# m101-power-supply.net
KiCad netlist of a schematic drawn in EAGLE
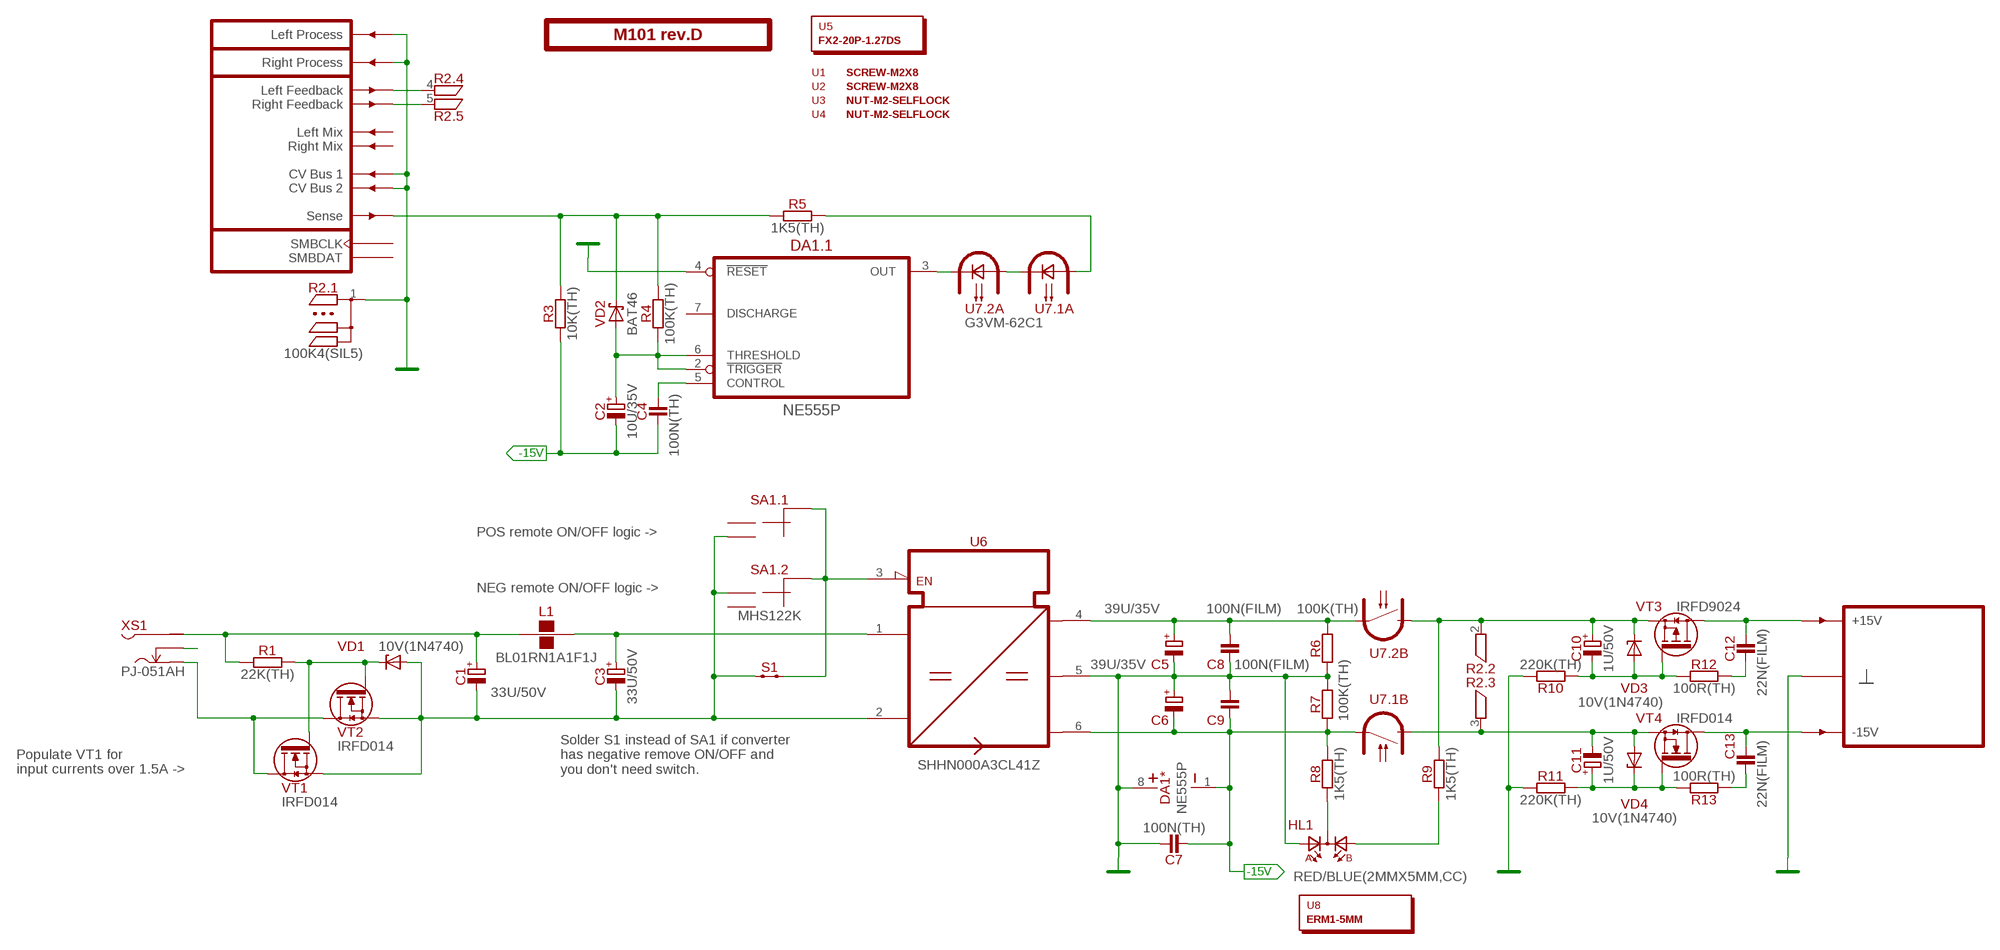
[diagram p0: schematic, sheet 1]

(export (version "E")
  (design (tool "Eeschema 10.0.6"))
  (components
    (comp (ref "C1")
      (value "33U/50V")
      (footprint "eagle-import:E3,5-8")
      (libsource (lib "eagle-import") (part "?33U/50V"))
    )
    (comp (ref "C2")
      (value "10U/35V")
      (footprint "eagle-import:E2-5")
      (libsource (lib "eagle-import") (part "?10U/35V"))
    )
    (comp (ref "C3")
      (value "33U/50V")
      (footprint "eagle-import:E3,5-8")
      (libsource (lib "eagle-import") (part "?33U/50V"))
    )
    (comp (ref "C4")
      (value "100N(TH)")
      (footprint "eagle-import:C050-024X044")
      (libsource (lib "eagle-import") (part "?100N(TH)"))
    )
    (comp (ref "C5")
      (value "39U/35V")
      (footprint "eagle-import:E3,5-8")
      (libsource (lib "eagle-import") (part "?39U/35V"))
    )
    (comp (ref "C6")
      (value "39U/35V")
      (footprint "eagle-import:E3,5-8")
      (libsource (lib "eagle-import") (part "?39U/35V"))
    )
    (comp (ref "C7")
      (value "100N(TH)")
      (footprint "eagle-import:C050-024X044")
      (libsource (lib "eagle-import") (part "?100N(TH)"))
    )
    (comp (ref "C8")
      (value "100N(FILM)")
      (footprint "eagle-import:C050-025X075")
      (libsource (lib "eagle-import") (part "?100N(FILM)"))
    )
    (comp (ref "C9")
      (value "100N(FILM)")
      (footprint "eagle-import:C050-025X075")
      (libsource (lib "eagle-import") (part "?100N(FILM)"))
    )
    (comp (ref "C10")
      (value "1U/50V")
      (footprint "eagle-import:E1,5-4")
      (libsource (lib "eagle-import") (part "?1U/50V"))
    )
    (comp (ref "C11")
      (value "1U/50V")
      (footprint "eagle-import:E1,5-4")
      (libsource (lib "eagle-import") (part "?1U/50V"))
    )
    (comp (ref "C12")
      (value "22N(FILM)")
      (footprint "eagle-import:C050-025X075")
      (libsource (lib "eagle-import") (part "?22N(FILM)"))
    )
    (comp (ref "C13")
      (value "22N(FILM)")
      (footprint "eagle-import:C050-025X075")
      (libsource (lib "eagle-import") (part "?22N(FILM)"))
    )
    (comp (ref "DA1")
      (value "NE555P")
      (footprint "eagle-import:DIP-8")
      (libsource (lib "eagle-import") (part "NE555?P"))
    )
    (comp (ref "HL1")
      (value "RED/BLUE(2MMX5MM,CC)")
      (footprint "eagle-import:LED2X5-3PIN")
      (libsource (lib "eagle-import") (part "?(2MMX5MM,CC)RED/BLUE"))
    )
    (comp (ref "L1")
      (value "BL01RN1A1F1J")
      (footprint "eagle-import:BL01RN1A")
      (libsource (lib "eagle-import") (part "BL01RN1A?1F1J"))
    )
    (comp (ref "PCB1")
      (value "M101 rev.D")
      (footprint "eagle-import:ST2-BOARD-50-PSU")
      (libsource (lib "eagle-import") (part "ST2-BOARD-50-PSU"))
    )
    (comp (ref "R1")
      (value "22K(TH)")
      (footprint "eagle-import:R-0207_10")
      (libsource (lib "eagle-import") (part "?22K(TH)"))
    )
    (comp (ref "R2")
      (value "100K4(SIL5)")
      (footprint "eagle-import:R-SIL5")
      (libsource (lib "eagle-import") (part "?4(SIL5)100K"))
    )
    (comp (ref "R3")
      (value "10K(TH)")
      (footprint "eagle-import:R-0207_10")
      (libsource (lib "eagle-import") (part "?10K(TH)"))
    )
    (comp (ref "R4")
      (value "100K(TH)")
      (footprint "eagle-import:R-0207_10")
      (libsource (lib "eagle-import") (part "?100K(TH)"))
    )
    (comp (ref "R5")
      (value "1K5(TH)")
      (footprint "eagle-import:R-0207_10")
      (libsource (lib "eagle-import") (part "?1K5(TH)"))
    )
    (comp (ref "R6")
      (value "100K(TH)")
      (footprint "eagle-import:R-0207_10")
      (libsource (lib "eagle-import") (part "?100K(TH)"))
    )
    (comp (ref "R7")
      (value "100K(TH)")
      (footprint "eagle-import:R-0207_10")
      (libsource (lib "eagle-import") (part "?100K(TH)"))
    )
    (comp (ref "R8")
      (value "1K5(TH)")
      (footprint "eagle-import:R-0207_10")
      (libsource (lib "eagle-import") (part "?1K5(TH)"))
    )
    (comp (ref "R9")
      (value "1K5(TH)")
      (footprint "eagle-import:R-0207_10")
      (libsource (lib "eagle-import") (part "?1K5(TH)"))
    )
    (comp (ref "R10")
      (value "220K(TH)")
      (footprint "eagle-import:R-0207_10")
      (libsource (lib "eagle-import") (part "?220K(TH)"))
    )
    (comp (ref "R11")
      (value "220K(TH)")
      (footprint "eagle-import:R-0207_10")
      (libsource (lib "eagle-import") (part "?220K(TH)"))
    )
    (comp (ref "R12")
      (value "100R(TH)")
      (footprint "eagle-import:R-0207_10")
      (libsource (lib "eagle-import") (part "?100R(TH)"))
    )
    (comp (ref "R13")
      (value "100R(TH)")
      (footprint "eagle-import:R-0207_10")
      (libsource (lib "eagle-import") (part "?100R(TH)"))
    )
    (comp (ref "S1")
      (value "JUMPER-1POS-SOLDER")
      (footprint "eagle-import:JP1-SOLDER")
      (libsource (lib "eagle-import") (part "JUMPER-1POS-SOLDER"))
    )
    (comp (ref "SA1")
      (value "MHS122K")
      (footprint "eagle-import:APEM-MHS122K")
      (libsource (lib "eagle-import") (part "MHS122K"))
    )
    (comp (ref "U1")
      (value "SCREW-M2X8")
      (footprint "eagle-import:EMPTY")
      (libsource (lib "eagle-import") (part "?SCREW-M2X8"))
    )
    (comp (ref "U2")
      (value "SCREW-M2X8")
      (footprint "eagle-import:EMPTY")
      (libsource (lib "eagle-import") (part "?SCREW-M2X8"))
    )
    (comp (ref "U3")
      (value "NUT-M2-SELFLOCK")
      (footprint "eagle-import:EMPTY")
      (libsource (lib "eagle-import") (part "?NUT-M2-SELFLOCK"))
    )
    (comp (ref "U4")
      (value "NUT-M2-SELFLOCK")
      (footprint "eagle-import:EMPTY")
      (libsource (lib "eagle-import") (part "?NUT-M2-SELFLOCK"))
    )
    (comp (ref "U5")
      (value "FX2-20P-1.27DS")
      (footprint "eagle-import:EMPTY")
      (libsource (lib "eagle-import") (part "?FX2-20P-1.27DS"))
    )
    (comp (ref "U6")
      (value "SHHN000A3CL41Z")
      (footprint "eagle-import:DC_DC-C1")
      (libsource (lib "eagle-import") (part "SHHN000A3CL41Z"))
    )
    (comp (ref "U7")
      (value "G3VM-62C1")
      (footprint "eagle-import:DIL08")
      (libsource (lib "eagle-import") (part "G3VM-?2C61"))
    )
    (comp (ref "U8")
      (value "ERM1-5MM")
      (footprint "eagle-import:EMPTY")
      (libsource (lib "eagle-import") (part "?ERM1-5MM"))
    )
    (comp (ref "VD1")
      (value "10V(1N4740)")
      (footprint "eagle-import:DO41-10")
      (libsource (lib "eagle-import") (part "?10V(1N4740)"))
    )
    (comp (ref "VD2")
      (value "BAT46")
      (footprint "eagle-import:DO35-7")
      (libsource (lib "eagle-import") (part "?BAT46"))
    )
    (comp (ref "VD3")
      (value "10V(1N4740)")
      (footprint "eagle-import:DO41-10")
      (libsource (lib "eagle-import") (part "?10V(1N4740)"))
    )
    (comp (ref "VD4")
      (value "10V(1N4740)")
      (footprint "eagle-import:DO41-10")
      (libsource (lib "eagle-import") (part "?10V(1N4740)"))
    )
    (comp (ref "VT1")
      (value "IRFD014")
      (footprint "eagle-import:HVMDIP-4")
      (libsource (lib "eagle-import") (part "IRFD014"))
    )
    (comp (ref "VT2")
      (value "IRFD014")
      (footprint "eagle-import:HVMDIP-4")
      (libsource (lib "eagle-import") (part "IRFD014"))
    )
    (comp (ref "VT3")
      (value "IRFD9024")
      (footprint "eagle-import:HVMDIP-4")
      (libsource (lib "eagle-import") (part "IRFD9024"))
    )
    (comp (ref "VT4")
      (value "IRFD014")
      (footprint "eagle-import:HVMDIP-4")
      (libsource (lib "eagle-import") (part "IRFD014"))
    )
    (comp (ref "XS1")
      (value "PJ-051AH")
      (footprint "eagle-import:PJ-051AH")
      (libsource (lib "eagle-import") (part "PJ-051?AH"))
    )
  )
  (nets
    (net (code "1") (name "-15V") (class "Default")
      (node (ref "C2") (pin "-") (pinfunction "-_-") (pintype "passive"))
      (node (ref "C4") (pin "1") (pinfunction "1_1") (pintype "passive"))
      (node (ref "C6") (pin "-") (pinfunction "-_-") (pintype "passive"))
      (node (ref "C7") (pin "1") (pinfunction "1_1") (pintype "passive"))
      (node (ref "C9") (pin "1") (pinfunction "1_1") (pintype "passive"))
      (node (ref "DA1") (pin "1") (pinfunction "V-_1") (pintype "power_in"))
      (node (ref "R3") (pin "1") (pinfunction "1_1") (pintype "passive"))
      (node (ref "R7") (pin "1") (pinfunction "1_1") (pintype "passive"))
      (node (ref "R8") (pin "2") (pinfunction "2_2") (pintype "passive"))
      (node (ref "U6") (pin "6") (pinfunction "V-_6") (pintype "power_in"))
      (node (ref "U7") (pin "7") (pinfunction "S2_7") (pintype "passive"))
    )
    (net (code "2") (name "GND") (class "Default")
      (node (ref "C5") (pin "-") (pinfunction "-_-") (pintype "passive"))
      (node (ref "C6") (pin "+") (pinfunction "+_+") (pintype "passive"))
      (node (ref "C7") (pin "2") (pinfunction "2_2") (pintype "passive"))
      (node (ref "C8") (pin "1") (pinfunction "1_1") (pintype "passive"))
      (node (ref "C9") (pin "2") (pinfunction "2_2") (pintype "passive"))
      (node (ref "DA1") (pin "4") (pinfunction "~{RESET}_4") (pintype "input"))
      (node (ref "DA1") (pin "8") (pinfunction "V+_8") (pintype "power_in"))
      (node (ref "HL1") (pin "A1") (pinfunction "A1_A1") (pintype "passive"))
      (node (ref "PCB1") (pin "ACV1'") (pinfunction "CV1'_ACV1'") (pintype "bidirectional"))
      (node (ref "PCB1") (pin "ACV2'") (pinfunction "CV2'_ACV2'") (pintype "bidirectional"))
      (node (ref "PCB1") (pin "B4'") (pinfunction "GND_B4'") (pintype "bidirectional"))
      (node (ref "PCB1") (pin "B5'") (pinfunction "GND_B5'") (pintype "bidirectional"))
      (node (ref "PCB1") (pin "B6'") (pinfunction "GND_B6'") (pintype "bidirectional"))
      (node (ref "PCB1") (pin "B7'") (pinfunction "GND_B7'") (pintype "bidirectional"))
      (node (ref "PCB1") (pin "B8'") (pinfunction "GND_B8'") (pintype "bidirectional"))
      (node (ref "PCB1") (pin "BOUTL'") (pinfunction "OUTL_BOUTL'") (pintype "bidirectional"))
      (node (ref "PCB1") (pin "BOUTR'") (pinfunction "OUTR_BOUTR'") (pintype "bidirectional"))
      (node (ref "R10") (pin "2") (pinfunction "2_2") (pintype "passive"))
      (node (ref "R11") (pin "2") (pinfunction "2_2") (pintype "passive"))
      (node (ref "R2") (pin "1") (pinfunction "R_1") (pintype "passive"))
      (node (ref "R6") (pin "1") (pinfunction "1_1") (pintype "passive"))
      (node (ref "R7") (pin "2") (pinfunction "2_2") (pintype "passive"))
      (node (ref "U6") (pin "5") (pinfunction "GND_5") (pintype "power_in"))
    )
    (net (code "3") (name "Net-(C12-Pad1)") (class "Default")
      (node (ref "C12") (pin "1") (pinfunction "1_1") (pintype "passive"))
      (node (ref "R12") (pin "2") (pinfunction "2_2") (pintype "passive"))
    )
    (net (code "4") (name "Net-(C12-Pad2)") (class "Default")
      (node (ref "C12") (pin "2") (pinfunction "2_2") (pintype "passive"))
      (node (ref "PCB1") (pin "A+15'") (pinfunction "P+15V_A+15'") (pintype "bidirectional"))
      (node (ref "PCB1") (pin "B+15'") (pinfunction "P+15V_B+15'") (pintype "bidirectional"))
      (node (ref "VT3") (pin "1") (pinfunction "D_1") (pintype "bidirectional"))
      (node (ref "VT3") (pin "2") (pinfunction "D_2") (pintype "bidirectional"))
    )
    (net (code "5") (name "Net-(C13-Pad1)") (class "Default")
      (node (ref "C13") (pin "1") (pinfunction "1_1") (pintype "passive"))
      (node (ref "PCB1") (pin "A-15'") (pinfunction "P-15V_A-15'") (pintype "bidirectional"))
      (node (ref "PCB1") (pin "B-15'") (pinfunction "P-15V_B-15'") (pintype "bidirectional"))
      (node (ref "VT4") (pin "1") (pinfunction "D_1") (pintype "bidirectional"))
      (node (ref "VT4") (pin "2") (pinfunction "D_2") (pintype "bidirectional"))
    )
    (net (code "6") (name "Net-(C13-Pad2)") (class "Default")
      (node (ref "C13") (pin "2") (pinfunction "2_2") (pintype "passive"))
      (node (ref "R13") (pin "2") (pinfunction "2_2") (pintype "passive"))
    )
    (net (code "7") (name "Net-(DA1B-CONTROL)") (class "Default")
      (node (ref "C4") (pin "2") (pinfunction "2_2") (pintype "passive"))
      (node (ref "DA1") (pin "5") (pinfunction "CONTROL_5") (pintype "bidirectional"))
    )
    (net (code "8") (name "Net-(DA1B-OUT)") (class "Default")
      (node (ref "DA1") (pin "3") (pinfunction "OUT_3") (pintype "bidirectional"))
      (node (ref "U7") (pin "4") (pinfunction "C_4") (pintype "passive"))
    )
    (net (code "9") (name "Net-(DA1B-THRESHOLD)") (class "Default")
      (node (ref "C2") (pin "+") (pinfunction "+_+") (pintype "passive"))
      (node (ref "DA1") (pin "2") (pinfunction "~{TRIGGER}_2") (pintype "bidirectional"))
      (node (ref "DA1") (pin "6") (pinfunction "THRESHOLD_6") (pintype "bidirectional"))
      (node (ref "R4") (pin "1") (pinfunction "1_1") (pintype "passive"))
      (node (ref "VD2") (pin "A") (pinfunction "A_A") (pintype "passive"))
    )
    (net (code "10") (name "Net-(HL1-PadA2)") (class "Default")
      (node (ref "HL1") (pin "A2") (pinfunction "A2_A2") (pintype "passive"))
      (node (ref "R9") (pin "1") (pinfunction "1_1") (pintype "passive"))
    )
    (net (code "11") (name "Net-(HL1-PadK)") (class "Default")
      (node (ref "HL1") (pin "K") (pinfunction "K_K") (pintype "passive"))
      (node (ref "R8") (pin "1") (pinfunction "1_1") (pintype "passive"))
    )
    (net (code "12") (name "Net-(PCB1D-LFBK')") (class "Default")
      (node (ref "PCB1") (pin "ALFBK'") (pinfunction "LFBK'_ALFBK'") (pintype "bidirectional"))
      (node (ref "R2") (pin "4") (pinfunction "R_4") (pintype "passive"))
    )
    (net (code "13") (name "Net-(PCB1D-RFBK')") (class "Default")
      (node (ref "PCB1") (pin "ARFBK'") (pinfunction "RFBK'_ARFBK'") (pintype "bidirectional"))
      (node (ref "R2") (pin "5") (pinfunction "R_5") (pintype "passive"))
    )
    (net (code "14") (name "Net-(PCB1D-SENSE')") (class "Default")
      (node (ref "PCB1") (pin "BSENSE'") (pinfunction "SENSE'_BSENSE'") (pintype "bidirectional"))
      (node (ref "R3") (pin "2") (pinfunction "2_2") (pintype "passive"))
      (node (ref "R4") (pin "2") (pinfunction "2_2") (pintype "passive"))
      (node (ref "R5") (pin "1") (pinfunction "1_1") (pintype "passive"))
      (node (ref "VD2") (pin "C") (pinfunction "C_C") (pintype "passive"))
    )
    (net (code "15") (name "Net-(R2B-R)") (class "Default")
      (node (ref "C10") (pin "+") (pinfunction "+_+") (pintype "passive"))
      (node (ref "R2") (pin "2") (pinfunction "R_2") (pintype "passive"))
      (node (ref "R9") (pin "2") (pinfunction "2_2") (pintype "passive"))
      (node (ref "U7") (pin "6") (pinfunction "S1_6") (pintype "passive"))
      (node (ref "VD3") (pin "C") (pinfunction "C_C") (pintype "passive"))
      (node (ref "VT3") (pin "4") (pinfunction "S_4") (pintype "bidirectional"))
    )
    (net (code "16") (name "Net-(R2C-R)") (class "Default")
      (node (ref "C11") (pin "-") (pinfunction "-_-") (pintype "passive"))
      (node (ref "R2") (pin "3") (pinfunction "R_3") (pintype "passive"))
      (node (ref "U7") (pin "8") (pinfunction "S1_8") (pintype "passive"))
      (node (ref "VD4") (pin "A") (pinfunction "A_A") (pintype "passive"))
      (node (ref "VT4") (pin "4") (pinfunction "S_4") (pintype "bidirectional"))
    )
    (net (code "17") (name "Net-(SA1A-CM)") (class "Default")
      (node (ref "S1") (pin "2") (pinfunction "2_2") (pintype "passive"))
      (node (ref "SA1") (pin "CMN") (pinfunction "CM_CMN") (pintype "passive"))
      (node (ref "SA1") (pin "CMN'") (pinfunction "CM_CMN'") (pintype "passive"))
      (node (ref "U6") (pin "3") (pinfunction "EN_3") (pintype "bidirectional"))
    )
    (net (code "18") (name "Net-(SA1B-1)") (class "Default")
      (node (ref "C1") (pin "-") (pinfunction "-_-") (pintype "passive"))
      (node (ref "C3") (pin "-") (pinfunction "-_-") (pintype "passive"))
      (node (ref "S1") (pin "1") (pinfunction "1_1") (pintype "passive"))
      (node (ref "SA1") (pin "1'") (pinfunction "1_1'") (pintype "passive"))
      (node (ref "SA1") (pin "2") (pinfunction "2_2") (pintype "passive"))
      (node (ref "U6") (pin "2") (pinfunction "IN-_2") (pintype "power_in"))
      (node (ref "VD1") (pin "A") (pinfunction "A_A") (pintype "passive"))
      (node (ref "VT1") (pin "4") (pinfunction "S_4") (pintype "bidirectional"))
      (node (ref "VT2") (pin "4") (pinfunction "S_4") (pintype "bidirectional"))
    )
    (net (code "19") (name "Net-(U6-IN+)") (class "Default")
      (node (ref "C3") (pin "+") (pinfunction "+_+") (pintype "passive"))
      (node (ref "L1") (pin "2") (pinfunction "2_2") (pintype "passive"))
      (node (ref "U6") (pin "1") (pinfunction "IN+_1") (pintype "power_in"))
    )
    (net (code "20") (name "Net-(U6-V+)") (class "Default")
      (node (ref "C5") (pin "+") (pinfunction "+_+") (pintype "passive"))
      (node (ref "C8") (pin "2") (pinfunction "2_2") (pintype "passive"))
      (node (ref "R6") (pin "2") (pinfunction "2_2") (pintype "passive"))
      (node (ref "U6") (pin "4") (pinfunction "V+_4") (pintype "power_in"))
      (node (ref "U7") (pin "5") (pinfunction "S2_5") (pintype "passive"))
    )
    (net (code "21") (name "Net-(U7A-A)") (class "Default")
      (node (ref "R5") (pin "2") (pinfunction "2_2") (pintype "passive"))
      (node (ref "U7") (pin "1") (pinfunction "A_1") (pintype "passive"))
    )
    (net (code "22") (name "Net-(U7A-C)") (class "Default")
      (node (ref "U7") (pin "2") (pinfunction "C_2") (pintype "passive"))
      (node (ref "U7") (pin "3") (pinfunction "A_3") (pintype "passive"))
    )
    (net (code "23") (name "Net-(VT1-G)") (class "Default")
      (node (ref "R1") (pin "2") (pinfunction "2_2") (pintype "passive"))
      (node (ref "VD1") (pin "C") (pinfunction "C_C") (pintype "passive"))
      (node (ref "VT1") (pin "3") (pinfunction "G_3") (pintype "bidirectional"))
      (node (ref "VT2") (pin "3") (pinfunction "G_3") (pintype "bidirectional"))
    )
    (net (code "24") (name "Net-(VT3-G)") (class "Default")
      (node (ref "C10") (pin "-") (pinfunction "-_-") (pintype "passive"))
      (node (ref "R10") (pin "1") (pinfunction "1_1") (pintype "passive"))
      (node (ref "R12") (pin "1") (pinfunction "1_1") (pintype "passive"))
      (node (ref "VD3") (pin "A") (pinfunction "A_A") (pintype "passive"))
      (node (ref "VT3") (pin "3") (pinfunction "G_3") (pintype "bidirectional"))
    )
    (net (code "25") (name "Net-(VT4-G)") (class "Default")
      (node (ref "C11") (pin "+") (pinfunction "+_+") (pintype "passive"))
      (node (ref "R11") (pin "1") (pinfunction "1_1") (pintype "passive"))
      (node (ref "R13") (pin "1") (pinfunction "1_1") (pintype "passive"))
      (node (ref "VD4") (pin "C") (pinfunction "C_C") (pintype "passive"))
      (node (ref "VT4") (pin "3") (pinfunction "G_3") (pintype "bidirectional"))
    )
    (net (code "26") (name "Net-(XS1-P)") (class "Default")
      (node (ref "C1") (pin "+") (pinfunction "+_+") (pintype "passive"))
      (node (ref "L1") (pin "1") (pinfunction "1_1") (pintype "passive"))
      (node (ref "R1") (pin "1") (pinfunction "1_1") (pintype "passive"))
      (node (ref "XS1") (pin "1") (pinfunction "P_1") (pintype "passive"))
    )
    (net (code "27") (name "Net-(XS1-S)") (class "Default")
      (node (ref "VT1") (pin "1") (pinfunction "D_1") (pintype "bidirectional"))
      (node (ref "VT1") (pin "2") (pinfunction "D_2") (pintype "bidirectional"))
      (node (ref "VT2") (pin "1") (pinfunction "D_1") (pintype "bidirectional"))
      (node (ref "VT2") (pin "2") (pinfunction "D_2") (pintype "bidirectional"))
      (node (ref "XS1") (pin "3") (pinfunction "S_3") (pintype "passive"))
    )
    (net (code "28") (name "unconnected-(DA1B-DISCHARGE-Pad7)") (class "Default")
      (node (ref "DA1") (pin "7") (pinfunction "DISCHARGE_7") (pintype "bidirectional"))
    )
    (net (code "29") (name "unconnected-(PCB1D-LMIX'-PadALMIX')") (class "Default")
      (node (ref "PCB1") (pin "ALMIX'") (pinfunction "LMIX'_ALMIX'") (pintype "bidirectional"))
    )
    (net (code "30") (name "unconnected-(PCB1D-RMIX'-PadARMIX')") (class "Default")
      (node (ref "PCB1") (pin "ARMIX'") (pinfunction "RMIX'_ARMIX'") (pintype "bidirectional"))
    )
    (net (code "31") (name "unconnected-(PCB1E-SMBCLK-PadASMBCLK')") (class "Default")
      (node (ref "PCB1") (pin "ASMBCLK'") (pinfunction "SMBCLK_ASMBCLK'") (pintype "bidirectional"))
    )
    (net (code "32") (name "unconnected-(PCB1E-SMBDAT-PadASMBDAT')") (class "Default")
      (node (ref "PCB1") (pin "ASMBDAT'") (pinfunction "SMBDAT_ASMBDAT'") (pintype "bidirectional"))
    )
    (net (code "33") (name "unconnected-(SA1-Pad1)") (class "Default")
      (node (ref "SA1") (pin "1") (pinfunction "1_1") (pintype "passive"))
    )
    (net (code "34") (name "unconnected-(SA1B-2-Pad2')") (class "Default")
      (node (ref "SA1") (pin "2'") (pinfunction "2_2'") (pintype "passive"))
    )
    (net (code "35") (name "unconnected-(XS1-SS-Pad2)") (class "Default")
      (node (ref "XS1") (pin "2") (pinfunction "SS_2") (pintype "passive"))
    )
  )
)
